# TemperatureSensorBlock.net
KiCad netlist of a schematic drawn in Altium Designer
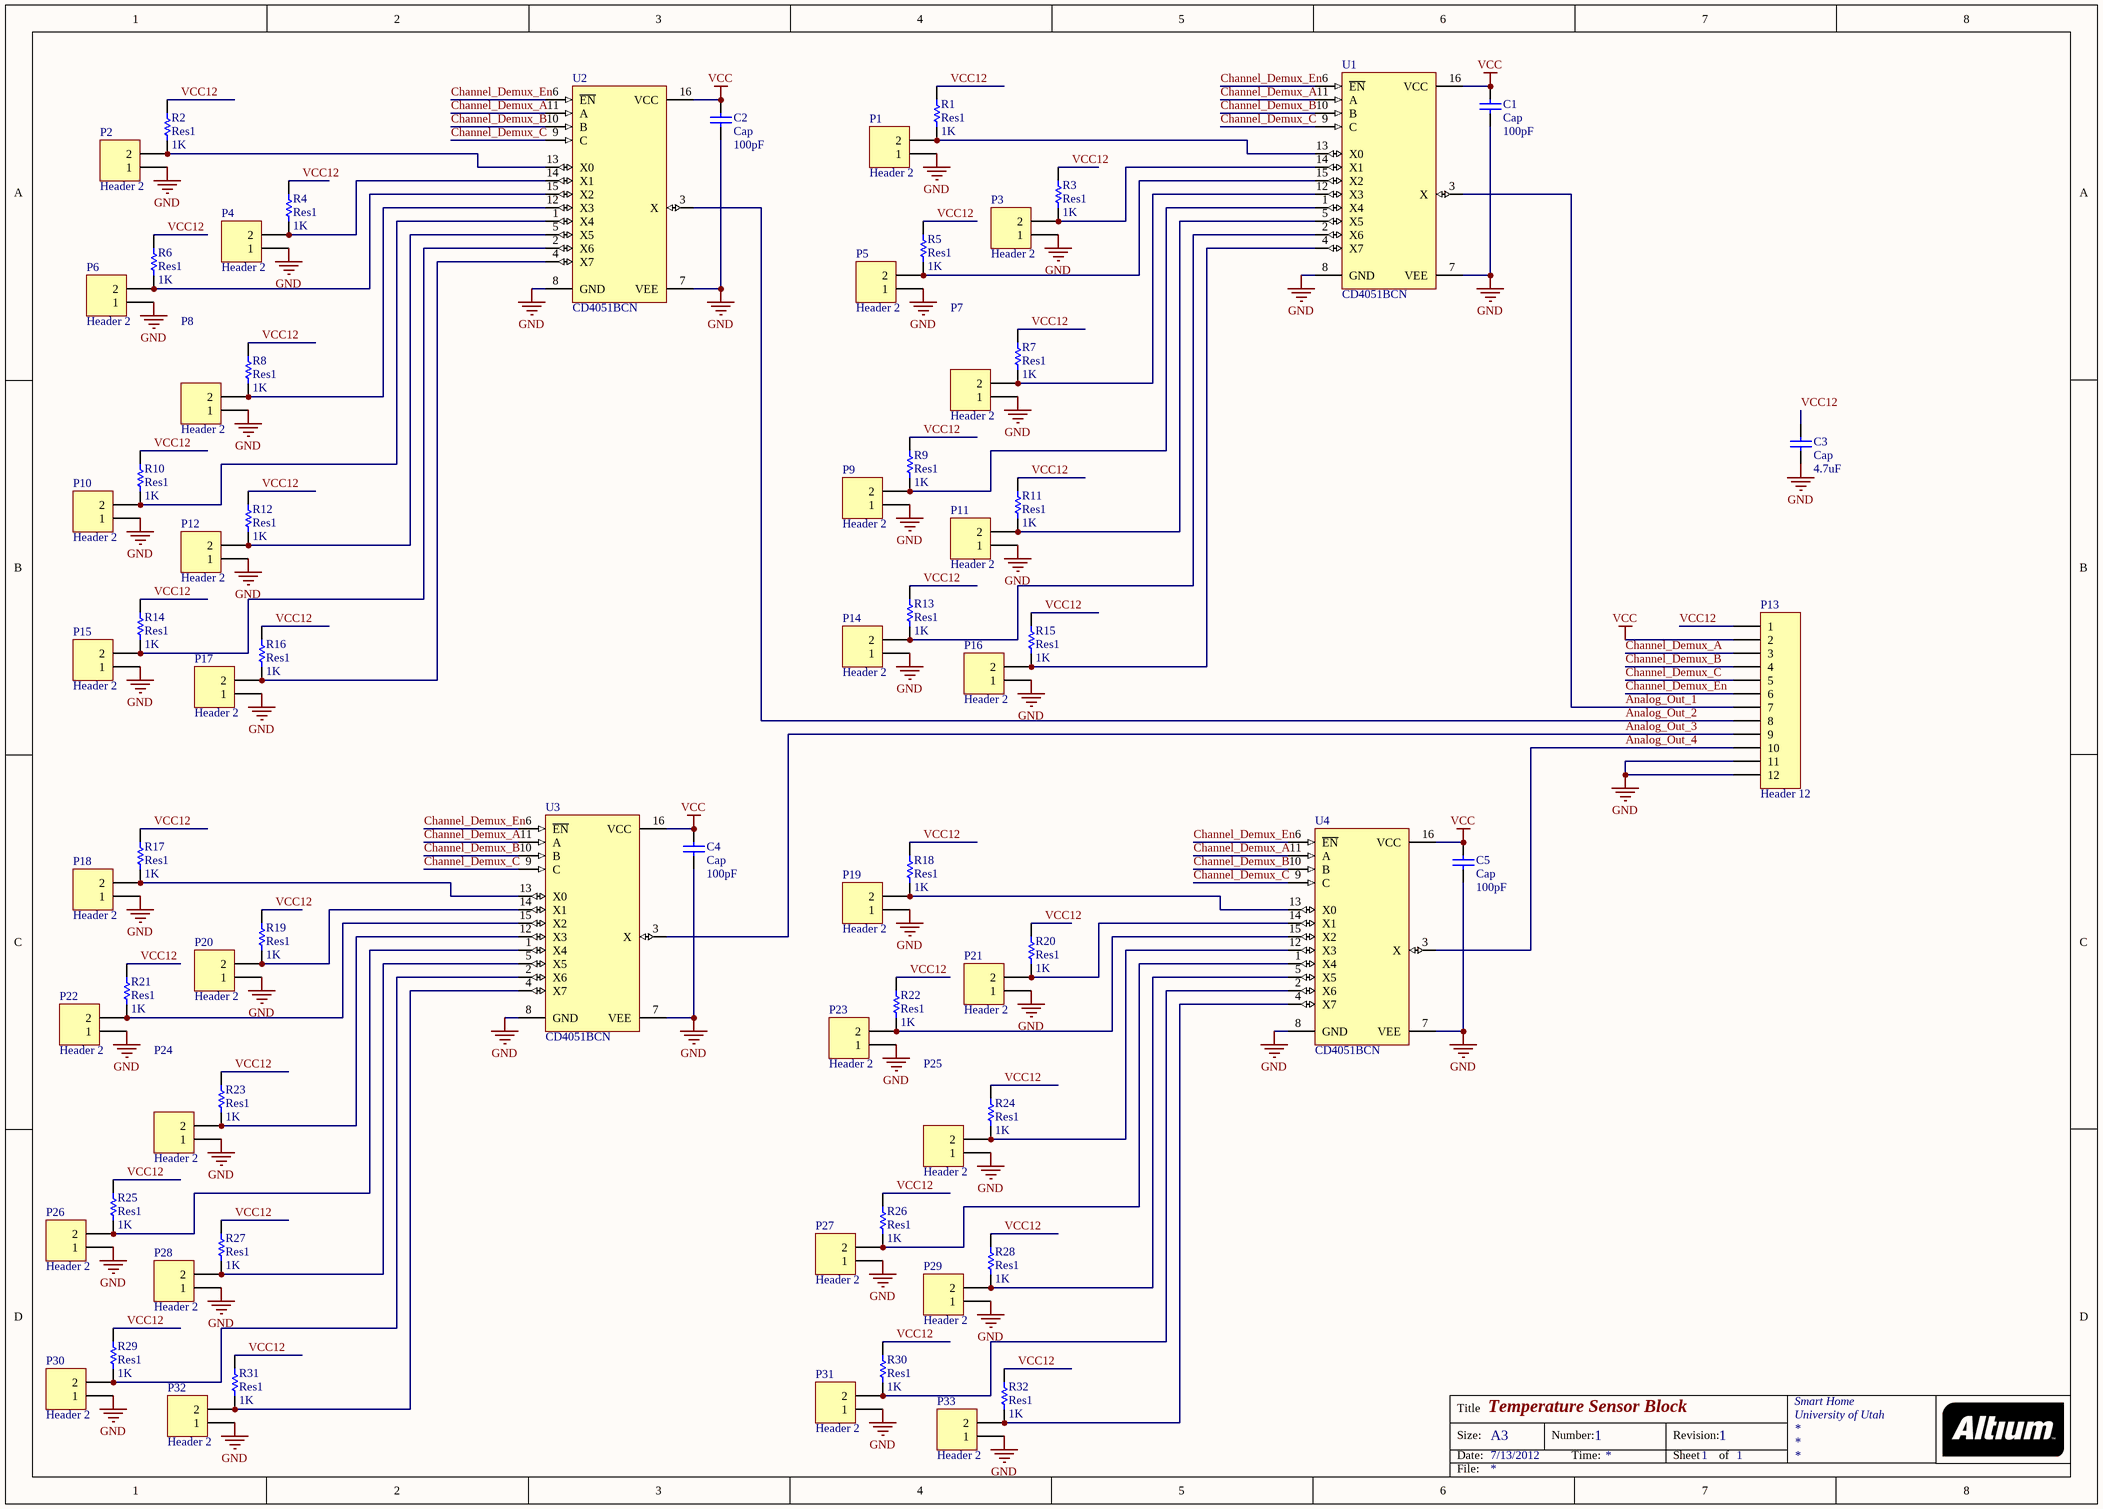
[diagram p0: TemperatureSensorBlock.SchDoc]

(export (version "E")
  (design (tool "Eeschema 10.0.6"))
  (components
    (comp (ref "C1")
      (value "Cap")
      (footprint "RAD-0.3")
      (description "Capacitor")
      (fields (field (name "ALTIUM_VALUE") "100pF") (field (name "PUBLISHER") "Altium Limited"))
      (libsource (lib "Miscellaneous Devices") (part "Cap"))
    )
    (comp (ref "C2")
      (value "Cap")
      (footprint "RAD-0.3")
      (description "Capacitor")
      (fields (field (name "ALTIUM_VALUE") "100pF") (field (name "PUBLISHER") "Altium Limited"))
      (libsource (lib "Miscellaneous Devices") (part "Cap"))
    )
    (comp (ref "C3")
      (value "Cap")
      (footprint "RAD-0.3")
      (description "Capacitor")
      (fields (field (name "ALTIUM_VALUE") "4.7uF") (field (name "PUBLISHER") "Altium Limited"))
      (libsource (lib "Miscellaneous Devices") (part "Cap"))
    )
    (comp (ref "C4")
      (value "Cap")
      (footprint "RAD-0.3")
      (description "Capacitor")
      (fields (field (name "ALTIUM_VALUE") "100pF") (field (name "PUBLISHER") "Altium Limited"))
      (libsource (lib "Miscellaneous Devices") (part "Cap"))
    )
    (comp (ref "C5")
      (value "Cap")
      (footprint "RAD-0.3")
      (description "Capacitor")
      (fields (field (name "ALTIUM_VALUE") "100pF") (field (name "PUBLISHER") "Altium Limited"))
      (libsource (lib "Miscellaneous Devices") (part "Cap"))
    )
    (comp (ref "P1")
      (value "Header 2")
      (footprint "HDR1X2")
      (description "Header, 2-Pin")
      (fields (field (name "PUBLISHER") "Altium Limited"))
      (libsource (lib "Miscellaneous Connectors") (part "Header 2"))
    )
    (comp (ref "P2")
      (value "Header 2")
      (footprint "HDR1X2")
      (description "Header, 2-Pin")
      (fields (field (name "PUBLISHER") "Altium Limited"))
      (libsource (lib "Miscellaneous Connectors") (part "Header 2"))
    )
    (comp (ref "P3")
      (value "Header 2")
      (footprint "HDR1X2")
      (description "Header, 2-Pin")
      (fields (field (name "PUBLISHER") "Altium Limited"))
      (libsource (lib "Miscellaneous Connectors") (part "Header 2"))
    )
    (comp (ref "P4")
      (value "Header 2")
      (footprint "HDR1X2")
      (description "Header, 2-Pin")
      (fields (field (name "PUBLISHER") "Altium Limited"))
      (libsource (lib "Miscellaneous Connectors") (part "Header 2"))
    )
    (comp (ref "P5")
      (value "Header 2")
      (footprint "HDR1X2")
      (description "Header, 2-Pin")
      (fields (field (name "PUBLISHER") "Altium Limited"))
      (libsource (lib "Miscellaneous Connectors") (part "Header 2"))
    )
    (comp (ref "P6")
      (value "Header 2")
      (footprint "HDR1X2")
      (description "Header, 2-Pin")
      (fields (field (name "PUBLISHER") "Altium Limited"))
      (libsource (lib "Miscellaneous Connectors") (part "Header 2"))
    )
    (comp (ref "P7")
      (value "Header 2")
      (footprint "HDR1X2")
      (description "Header, 2-Pin")
      (fields (field (name "PUBLISHER") "Altium Limited"))
      (libsource (lib "Miscellaneous Connectors") (part "Header 2"))
    )
    (comp (ref "P8")
      (value "Header 2")
      (footprint "HDR1X2")
      (description "Header, 2-Pin")
      (fields (field (name "PUBLISHER") "Altium Limited"))
      (libsource (lib "Miscellaneous Connectors") (part "Header 2"))
    )
    (comp (ref "P9")
      (value "Header 2")
      (footprint "HDR1X2")
      (description "Header, 2-Pin")
      (fields (field (name "PUBLISHER") "Altium Limited"))
      (libsource (lib "Miscellaneous Connectors") (part "Header 2"))
    )
    (comp (ref "P10")
      (value "Header 2")
      (footprint "HDR1X2")
      (description "Header, 2-Pin")
      (fields (field (name "PUBLISHER") "Altium Limited"))
      (libsource (lib "Miscellaneous Connectors") (part "Header 2"))
    )
    (comp (ref "P11")
      (value "Header 2")
      (footprint "HDR1X2")
      (description "Header, 2-Pin")
      (fields (field (name "PUBLISHER") "Altium Limited"))
      (libsource (lib "Miscellaneous Connectors") (part "Header 2"))
    )
    (comp (ref "P12")
      (value "Header 2")
      (footprint "HDR1X2")
      (description "Header, 2-Pin")
      (fields (field (name "PUBLISHER") "Altium Limited"))
      (libsource (lib "Miscellaneous Connectors") (part "Header 2"))
    )
    (comp (ref "P13")
      (value "Header 12")
      (footprint "HDR1X12")
      (description "Header, 12-Pin")
      (fields (field (name "PUBLISHER") "Altium Limited"))
      (libsource (lib "Miscellaneous Connectors") (part "Header 12"))
    )
    (comp (ref "P14")
      (value "Header 2")
      (footprint "HDR1X2")
      (description "Header, 2-Pin")
      (fields (field (name "PUBLISHER") "Altium Limited"))
      (libsource (lib "Miscellaneous Connectors") (part "Header 2"))
    )
    (comp (ref "P15")
      (value "Header 2")
      (footprint "HDR1X2")
      (description "Header, 2-Pin")
      (fields (field (name "PUBLISHER") "Altium Limited"))
      (libsource (lib "Miscellaneous Connectors") (part "Header 2"))
    )
    (comp (ref "P16")
      (value "Header 2")
      (footprint "HDR1X2")
      (description "Header, 2-Pin")
      (fields (field (name "PUBLISHER") "Altium Limited"))
      (libsource (lib "Miscellaneous Connectors") (part "Header 2"))
    )
    (comp (ref "P17")
      (value "Header 2")
      (footprint "HDR1X2")
      (description "Header, 2-Pin")
      (fields (field (name "PUBLISHER") "Altium Limited"))
      (libsource (lib "Miscellaneous Connectors") (part "Header 2"))
    )
    (comp (ref "P18")
      (value "Header 2")
      (footprint "HDR1X2")
      (description "Header, 2-Pin")
      (fields (field (name "PUBLISHER") "Altium Limited"))
      (libsource (lib "Miscellaneous Connectors") (part "Header 2"))
    )
    (comp (ref "P19")
      (value "Header 2")
      (footprint "HDR1X2")
      (description "Header, 2-Pin")
      (fields (field (name "PUBLISHER") "Altium Limited"))
      (libsource (lib "Miscellaneous Connectors") (part "Header 2"))
    )
    (comp (ref "P20")
      (value "Header 2")
      (footprint "HDR1X2")
      (description "Header, 2-Pin")
      (fields (field (name "PUBLISHER") "Altium Limited"))
      (libsource (lib "Miscellaneous Connectors") (part "Header 2"))
    )
    (comp (ref "P21")
      (value "Header 2")
      (footprint "HDR1X2")
      (description "Header, 2-Pin")
      (fields (field (name "PUBLISHER") "Altium Limited"))
      (libsource (lib "Miscellaneous Connectors") (part "Header 2"))
    )
    (comp (ref "P22")
      (value "Header 2")
      (footprint "HDR1X2")
      (description "Header, 2-Pin")
      (fields (field (name "PUBLISHER") "Altium Limited"))
      (libsource (lib "Miscellaneous Connectors") (part "Header 2"))
    )
    (comp (ref "P23")
      (value "Header 2")
      (footprint "HDR1X2")
      (description "Header, 2-Pin")
      (fields (field (name "PUBLISHER") "Altium Limited"))
      (libsource (lib "Miscellaneous Connectors") (part "Header 2"))
    )
    (comp (ref "P24")
      (value "Header 2")
      (footprint "HDR1X2")
      (description "Header, 2-Pin")
      (fields (field (name "PUBLISHER") "Altium Limited"))
      (libsource (lib "Miscellaneous Connectors") (part "Header 2"))
    )
    (comp (ref "P25")
      (value "Header 2")
      (footprint "HDR1X2")
      (description "Header, 2-Pin")
      (fields (field (name "PUBLISHER") "Altium Limited"))
      (libsource (lib "Miscellaneous Connectors") (part "Header 2"))
    )
    (comp (ref "P26")
      (value "Header 2")
      (footprint "HDR1X2")
      (description "Header, 2-Pin")
      (fields (field (name "PUBLISHER") "Altium Limited"))
      (libsource (lib "Miscellaneous Connectors") (part "Header 2"))
    )
    (comp (ref "P27")
      (value "Header 2")
      (footprint "HDR1X2")
      (description "Header, 2-Pin")
      (fields (field (name "PUBLISHER") "Altium Limited"))
      (libsource (lib "Miscellaneous Connectors") (part "Header 2"))
    )
    (comp (ref "P28")
      (value "Header 2")
      (footprint "HDR1X2")
      (description "Header, 2-Pin")
      (fields (field (name "PUBLISHER") "Altium Limited"))
      (libsource (lib "Miscellaneous Connectors") (part "Header 2"))
    )
    (comp (ref "P29")
      (value "Header 2")
      (footprint "HDR1X2")
      (description "Header, 2-Pin")
      (fields (field (name "PUBLISHER") "Altium Limited"))
      (libsource (lib "Miscellaneous Connectors") (part "Header 2"))
    )
    (comp (ref "P30")
      (value "Header 2")
      (footprint "HDR1X2")
      (description "Header, 2-Pin")
      (fields (field (name "PUBLISHER") "Altium Limited"))
      (libsource (lib "Miscellaneous Connectors") (part "Header 2"))
    )
    (comp (ref "P31")
      (value "Header 2")
      (footprint "HDR1X2")
      (description "Header, 2-Pin")
      (fields (field (name "PUBLISHER") "Altium Limited"))
      (libsource (lib "Miscellaneous Connectors") (part "Header 2"))
    )
    (comp (ref "P32")
      (value "Header 2")
      (footprint "HDR1X2")
      (description "Header, 2-Pin")
      (fields (field (name "PUBLISHER") "Altium Limited"))
      (libsource (lib "Miscellaneous Connectors") (part "Header 2"))
    )
    (comp (ref "P33")
      (value "Header 2")
      (footprint "HDR1X2")
      (description "Header, 2-Pin")
      (fields (field (name "PUBLISHER") "Altium Limited"))
      (libsource (lib "Miscellaneous Connectors") (part "Header 2"))
    )
    (comp (ref "R1")
      (value "Res1")
      (footprint "AXIAL-0.3")
      (description "Resistor")
      (fields (field (name "ALTIUM_VALUE") "1K") (field (name "PUBLISHER") "Altium Limited"))
      (libsource (lib "Miscellaneous Devices") (part "Res1"))
    )
    (comp (ref "R2")
      (value "Res1")
      (footprint "AXIAL-0.3")
      (description "Resistor")
      (fields (field (name "ALTIUM_VALUE") "1K") (field (name "PUBLISHER") "Altium Limited"))
      (libsource (lib "Miscellaneous Devices") (part "Res1"))
    )
    (comp (ref "R3")
      (value "Res1")
      (footprint "AXIAL-0.3")
      (description "Resistor")
      (fields (field (name "ALTIUM_VALUE") "1K") (field (name "PUBLISHER") "Altium Limited"))
      (libsource (lib "Miscellaneous Devices") (part "Res1"))
    )
    (comp (ref "R4")
      (value "Res1")
      (footprint "AXIAL-0.3")
      (description "Resistor")
      (fields (field (name "ALTIUM_VALUE") "1K") (field (name "PUBLISHER") "Altium Limited"))
      (libsource (lib "Miscellaneous Devices") (part "Res1"))
    )
    (comp (ref "R5")
      (value "Res1")
      (footprint "AXIAL-0.3")
      (description "Resistor")
      (fields (field (name "ALTIUM_VALUE") "1K") (field (name "PUBLISHER") "Altium Limited"))
      (libsource (lib "Miscellaneous Devices") (part "Res1"))
    )
    (comp (ref "R6")
      (value "Res1")
      (footprint "AXIAL-0.3")
      (description "Resistor")
      (fields (field (name "ALTIUM_VALUE") "1K") (field (name "PUBLISHER") "Altium Limited"))
      (libsource (lib "Miscellaneous Devices") (part "Res1"))
    )
    (comp (ref "R7")
      (value "Res1")
      (footprint "AXIAL-0.3")
      (description "Resistor")
      (fields (field (name "ALTIUM_VALUE") "1K") (field (name "PUBLISHER") "Altium Limited"))
      (libsource (lib "Miscellaneous Devices") (part "Res1"))
    )
    (comp (ref "R8")
      (value "Res1")
      (footprint "AXIAL-0.3")
      (description "Resistor")
      (fields (field (name "ALTIUM_VALUE") "1K") (field (name "PUBLISHER") "Altium Limited"))
      (libsource (lib "Miscellaneous Devices") (part "Res1"))
    )
    (comp (ref "R9")
      (value "Res1")
      (footprint "AXIAL-0.3")
      (description "Resistor")
      (fields (field (name "ALTIUM_VALUE") "1K") (field (name "PUBLISHER") "Altium Limited"))
      (libsource (lib "Miscellaneous Devices") (part "Res1"))
    )
    (comp (ref "R10")
      (value "Res1")
      (footprint "AXIAL-0.3")
      (description "Resistor")
      (fields (field (name "ALTIUM_VALUE") "1K") (field (name "PUBLISHER") "Altium Limited"))
      (libsource (lib "Miscellaneous Devices") (part "Res1"))
    )
    (comp (ref "R11")
      (value "Res1")
      (footprint "AXIAL-0.3")
      (description "Resistor")
      (fields (field (name "ALTIUM_VALUE") "1K") (field (name "PUBLISHER") "Altium Limited"))
      (libsource (lib "Miscellaneous Devices") (part "Res1"))
    )
    (comp (ref "R12")
      (value "Res1")
      (footprint "AXIAL-0.3")
      (description "Resistor")
      (fields (field (name "ALTIUM_VALUE") "1K") (field (name "PUBLISHER") "Altium Limited"))
      (libsource (lib "Miscellaneous Devices") (part "Res1"))
    )
    (comp (ref "R13")
      (value "Res1")
      (footprint "AXIAL-0.3")
      (description "Resistor")
      (fields (field (name "ALTIUM_VALUE") "1K") (field (name "PUBLISHER") "Altium Limited"))
      (libsource (lib "Miscellaneous Devices") (part "Res1"))
    )
    (comp (ref "R14")
      (value "Res1")
      (footprint "AXIAL-0.3")
      (description "Resistor")
      (fields (field (name "ALTIUM_VALUE") "1K") (field (name "PUBLISHER") "Altium Limited"))
      (libsource (lib "Miscellaneous Devices") (part "Res1"))
    )
    (comp (ref "R15")
      (value "Res1")
      (footprint "AXIAL-0.3")
      (description "Resistor")
      (fields (field (name "ALTIUM_VALUE") "1K") (field (name "PUBLISHER") "Altium Limited"))
      (libsource (lib "Miscellaneous Devices") (part "Res1"))
    )
    (comp (ref "R16")
      (value "Res1")
      (footprint "AXIAL-0.3")
      (description "Resistor")
      (fields (field (name "ALTIUM_VALUE") "1K") (field (name "PUBLISHER") "Altium Limited"))
      (libsource (lib "Miscellaneous Devices") (part "Res1"))
    )
    (comp (ref "R17")
      (value "Res1")
      (footprint "AXIAL-0.3")
      (description "Resistor")
      (fields (field (name "ALTIUM_VALUE") "1K") (field (name "PUBLISHER") "Altium Limited"))
      (libsource (lib "Miscellaneous Devices") (part "Res1"))
    )
    (comp (ref "R18")
      (value "Res1")
      (footprint "AXIAL-0.3")
      (description "Resistor")
      (fields (field (name "ALTIUM_VALUE") "1K") (field (name "PUBLISHER") "Altium Limited"))
      (libsource (lib "Miscellaneous Devices") (part "Res1"))
    )
    (comp (ref "R19")
      (value "Res1")
      (footprint "AXIAL-0.3")
      (description "Resistor")
      (fields (field (name "ALTIUM_VALUE") "1K") (field (name "PUBLISHER") "Altium Limited"))
      (libsource (lib "Miscellaneous Devices") (part "Res1"))
    )
    (comp (ref "R20")
      (value "Res1")
      (footprint "AXIAL-0.3")
      (description "Resistor")
      (fields (field (name "ALTIUM_VALUE") "1K") (field (name "PUBLISHER") "Altium Limited"))
      (libsource (lib "Miscellaneous Devices") (part "Res1"))
    )
    (comp (ref "R21")
      (value "Res1")
      (footprint "AXIAL-0.3")
      (description "Resistor")
      (fields (field (name "ALTIUM_VALUE") "1K") (field (name "PUBLISHER") "Altium Limited"))
      (libsource (lib "Miscellaneous Devices") (part "Res1"))
    )
    (comp (ref "R22")
      (value "Res1")
      (footprint "AXIAL-0.3")
      (description "Resistor")
      (fields (field (name "ALTIUM_VALUE") "1K") (field (name "PUBLISHER") "Altium Limited"))
      (libsource (lib "Miscellaneous Devices") (part "Res1"))
    )
    (comp (ref "R23")
      (value "Res1")
      (footprint "AXIAL-0.3")
      (description "Resistor")
      (fields (field (name "ALTIUM_VALUE") "1K") (field (name "PUBLISHER") "Altium Limited"))
      (libsource (lib "Miscellaneous Devices") (part "Res1"))
    )
    (comp (ref "R24")
      (value "Res1")
      (footprint "AXIAL-0.3")
      (description "Resistor")
      (fields (field (name "ALTIUM_VALUE") "1K") (field (name "PUBLISHER") "Altium Limited"))
      (libsource (lib "Miscellaneous Devices") (part "Res1"))
    )
    (comp (ref "R25")
      (value "Res1")
      (footprint "AXIAL-0.3")
      (description "Resistor")
      (fields (field (name "ALTIUM_VALUE") "1K") (field (name "PUBLISHER") "Altium Limited"))
      (libsource (lib "Miscellaneous Devices") (part "Res1"))
    )
    (comp (ref "R26")
      (value "Res1")
      (footprint "AXIAL-0.3")
      (description "Resistor")
      (fields (field (name "ALTIUM_VALUE") "1K") (field (name "PUBLISHER") "Altium Limited"))
      (libsource (lib "Miscellaneous Devices") (part "Res1"))
    )
    (comp (ref "R27")
      (value "Res1")
      (footprint "AXIAL-0.3")
      (description "Resistor")
      (fields (field (name "ALTIUM_VALUE") "1K") (field (name "PUBLISHER") "Altium Limited"))
      (libsource (lib "Miscellaneous Devices") (part "Res1"))
    )
    (comp (ref "R28")
      (value "Res1")
      (footprint "AXIAL-0.3")
      (description "Resistor")
      (fields (field (name "ALTIUM_VALUE") "1K") (field (name "PUBLISHER") "Altium Limited"))
      (libsource (lib "Miscellaneous Devices") (part "Res1"))
    )
    (comp (ref "R29")
      (value "Res1")
      (footprint "AXIAL-0.3")
      (description "Resistor")
      (fields (field (name "ALTIUM_VALUE") "1K") (field (name "PUBLISHER") "Altium Limited"))
      (libsource (lib "Miscellaneous Devices") (part "Res1"))
    )
    (comp (ref "R30")
      (value "Res1")
      (footprint "AXIAL-0.3")
      (description "Resistor")
      (fields (field (name "ALTIUM_VALUE") "1K") (field (name "PUBLISHER") "Altium Limited"))
      (libsource (lib "Miscellaneous Devices") (part "Res1"))
    )
    (comp (ref "R31")
      (value "Res1")
      (footprint "AXIAL-0.3")
      (description "Resistor")
      (fields (field (name "ALTIUM_VALUE") "1K") (field (name "PUBLISHER") "Altium Limited"))
      (libsource (lib "Miscellaneous Devices") (part "Res1"))
    )
    (comp (ref "R32")
      (value "Res1")
      (footprint "AXIAL-0.3")
      (description "Resistor")
      (fields (field (name "ALTIUM_VALUE") "1K") (field (name "PUBLISHER") "Altium Limited"))
      (libsource (lib "Miscellaneous Devices") (part "Res1"))
    )
    (comp (ref "U1")
      (value "CD4051BCN")
      (footprint "N16E")
      (description "8-Channel Analog Multiplexer/Demultiplexer")
      (fields (field (name "PUBLISHER") "Altium Limited"))
      (libsource (lib "FSC Logic Multiplexer") (part "CD4051BCN"))
    )
    (comp (ref "U2")
      (value "CD4051BCN")
      (footprint "N16E")
      (description "8-Channel Analog Multiplexer/Demultiplexer")
      (fields (field (name "PUBLISHER") "Altium Limited"))
      (libsource (lib "FSC Logic Multiplexer") (part "CD4051BCN"))
    )
    (comp (ref "U3")
      (value "CD4051BCN")
      (footprint "N16E")
      (description "8-Channel Analog Multiplexer/Demultiplexer")
      (fields (field (name "PUBLISHER") "Altium Limited"))
      (libsource (lib "FSC Logic Multiplexer") (part "CD4051BCN"))
    )
    (comp (ref "U4")
      (value "CD4051BCN")
      (footprint "N16E")
      (description "8-Channel Analog Multiplexer/Demultiplexer")
      (fields (field (name "PUBLISHER") "Altium Limited"))
      (libsource (lib "FSC Logic Multiplexer") (part "CD4051BCN"))
    )
  )
  (nets
    (net (code "1") (name "/Analog_Out_1") (class "Default")
      (node (ref "P13") (pin "7") (pinfunction "7_7") (pintype "passive"))
      (node (ref "U1") (pin "3") (pinfunction "X_3") (pintype "bidirectional"))
    )
    (net (code "2") (name "/Analog_Out_2") (class "Default")
      (node (ref "P13") (pin "8") (pinfunction "8_8") (pintype "passive"))
      (node (ref "U2") (pin "3") (pinfunction "X_3") (pintype "bidirectional"))
    )
    (net (code "3") (name "/Analog_Out_3") (class "Default")
      (node (ref "P13") (pin "9") (pinfunction "9_9") (pintype "passive"))
      (node (ref "U3") (pin "3") (pinfunction "X_3") (pintype "bidirectional"))
    )
    (net (code "4") (name "/Analog_Out_4") (class "Default")
      (node (ref "P13") (pin "10") (pinfunction "10_10") (pintype "passive"))
      (node (ref "U4") (pin "3") (pinfunction "X_3") (pintype "bidirectional"))
    )
    (net (code "5") (name "/Channel_Demux_A") (class "Default")
      (node (ref "P13") (pin "3") (pinfunction "3_3") (pintype "passive"))
      (node (ref "U1") (pin "11") (pinfunction "A_11") (pintype "input"))
      (node (ref "U2") (pin "11") (pinfunction "A_11") (pintype "input"))
      (node (ref "U3") (pin "11") (pinfunction "A_11") (pintype "input"))
      (node (ref "U4") (pin "11") (pinfunction "A_11") (pintype "input"))
    )
    (net (code "6") (name "/Channel_Demux_B") (class "Default")
      (node (ref "P13") (pin "4") (pinfunction "4_4") (pintype "passive"))
      (node (ref "U1") (pin "10") (pinfunction "B_10") (pintype "input"))
      (node (ref "U2") (pin "10") (pinfunction "B_10") (pintype "input"))
      (node (ref "U3") (pin "10") (pinfunction "B_10") (pintype "input"))
      (node (ref "U4") (pin "10") (pinfunction "B_10") (pintype "input"))
    )
    (net (code "7") (name "/Channel_Demux_C") (class "Default")
      (node (ref "P13") (pin "5") (pinfunction "5_5") (pintype "passive"))
      (node (ref "U1") (pin "9") (pinfunction "C_9") (pintype "input"))
      (node (ref "U2") (pin "9") (pinfunction "C_9") (pintype "input"))
      (node (ref "U3") (pin "9") (pinfunction "C_9") (pintype "input"))
      (node (ref "U4") (pin "9") (pinfunction "C_9") (pintype "input"))
    )
    (net (code "8") (name "/Channel_Demux_En") (class "Default")
      (node (ref "P13") (pin "6") (pinfunction "6_6") (pintype "passive"))
      (node (ref "U1") (pin "6") (pinfunction "~{EN}_6") (pintype "input"))
      (node (ref "U2") (pin "6") (pinfunction "~{EN}_6") (pintype "input"))
      (node (ref "U3") (pin "6") (pinfunction "~{EN}_6") (pintype "input"))
      (node (ref "U4") (pin "6") (pinfunction "~{EN}_6") (pintype "input"))
    )
    (net (code "9") (name "/VCC12") (class "Default")
      (node (ref "C3") (pin "2") (pinfunction "2_2") (pintype "passive"))
      (node (ref "P13") (pin "1") (pinfunction "1_1") (pintype "passive"))
      (node (ref "R1") (pin "2") (pinfunction "2_2") (pintype "passive"))
      (node (ref "R10") (pin "2") (pinfunction "2_2") (pintype "passive"))
      (node (ref "R11") (pin "2") (pinfunction "2_2") (pintype "passive"))
      (node (ref "R12") (pin "2") (pinfunction "2_2") (pintype "passive"))
      (node (ref "R13") (pin "2") (pinfunction "2_2") (pintype "passive"))
      (node (ref "R14") (pin "2") (pinfunction "2_2") (pintype "passive"))
      (node (ref "R15") (pin "2") (pinfunction "2_2") (pintype "passive"))
      (node (ref "R16") (pin "2") (pinfunction "2_2") (pintype "passive"))
      (node (ref "R17") (pin "2") (pinfunction "2_2") (pintype "passive"))
      (node (ref "R18") (pin "2") (pinfunction "2_2") (pintype "passive"))
      (node (ref "R19") (pin "2") (pinfunction "2_2") (pintype "passive"))
      (node (ref "R2") (pin "2") (pinfunction "2_2") (pintype "passive"))
      (node (ref "R20") (pin "2") (pinfunction "2_2") (pintype "passive"))
      (node (ref "R21") (pin "2") (pinfunction "2_2") (pintype "passive"))
      (node (ref "R22") (pin "2") (pinfunction "2_2") (pintype "passive"))
      (node (ref "R23") (pin "2") (pinfunction "2_2") (pintype "passive"))
      (node (ref "R24") (pin "2") (pinfunction "2_2") (pintype "passive"))
      (node (ref "R25") (pin "2") (pinfunction "2_2") (pintype "passive"))
      (node (ref "R26") (pin "2") (pinfunction "2_2") (pintype "passive"))
      (node (ref "R27") (pin "2") (pinfunction "2_2") (pintype "passive"))
      (node (ref "R28") (pin "2") (pinfunction "2_2") (pintype "passive"))
      (node (ref "R29") (pin "2") (pinfunction "2_2") (pintype "passive"))
      (node (ref "R3") (pin "2") (pinfunction "2_2") (pintype "passive"))
      (node (ref "R30") (pin "2") (pinfunction "2_2") (pintype "passive"))
      (node (ref "R31") (pin "2") (pinfunction "2_2") (pintype "passive"))
      (node (ref "R32") (pin "2") (pinfunction "2_2") (pintype "passive"))
      (node (ref "R4") (pin "2") (pinfunction "2_2") (pintype "passive"))
      (node (ref "R5") (pin "2") (pinfunction "2_2") (pintype "passive"))
      (node (ref "R6") (pin "2") (pinfunction "2_2") (pintype "passive"))
      (node (ref "R7") (pin "2") (pinfunction "2_2") (pintype "passive"))
      (node (ref "R8") (pin "2") (pinfunction "2_2") (pintype "passive"))
      (node (ref "R9") (pin "2") (pinfunction "2_2") (pintype "passive"))
    )
    (net (code "10") (name "GND") (class "Default")
      (node (ref "C1") (pin "1") (pinfunction "1_1") (pintype "passive"))
      (node (ref "C2") (pin "1") (pinfunction "1_1") (pintype "passive"))
      (node (ref "C3") (pin "1") (pinfunction "1_1") (pintype "passive"))
      (node (ref "C4") (pin "1") (pinfunction "1_1") (pintype "passive"))
      (node (ref "C5") (pin "1") (pinfunction "1_1") (pintype "passive"))
      (node (ref "P1") (pin "1") (pinfunction "1_1") (pintype "passive"))
      (node (ref "P10") (pin "1") (pinfunction "1_1") (pintype "passive"))
      (node (ref "P11") (pin "1") (pinfunction "1_1") (pintype "passive"))
      (node (ref "P12") (pin "1") (pinfunction "1_1") (pintype "passive"))
      (node (ref "P13") (pin "11") (pinfunction "11_11") (pintype "passive"))
      (node (ref "P13") (pin "12") (pinfunction "12_12") (pintype "passive"))
      (node (ref "P14") (pin "1") (pinfunction "1_1") (pintype "passive"))
      (node (ref "P15") (pin "1") (pinfunction "1_1") (pintype "passive"))
      (node (ref "P16") (pin "1") (pinfunction "1_1") (pintype "passive"))
      (node (ref "P17") (pin "1") (pinfunction "1_1") (pintype "passive"))
      (node (ref "P18") (pin "1") (pinfunction "1_1") (pintype "passive"))
      (node (ref "P19") (pin "1") (pinfunction "1_1") (pintype "passive"))
      (node (ref "P2") (pin "1") (pinfunction "1_1") (pintype "passive"))
      (node (ref "P20") (pin "1") (pinfunction "1_1") (pintype "passive"))
      (node (ref "P21") (pin "1") (pinfunction "1_1") (pintype "passive"))
      (node (ref "P22") (pin "1") (pinfunction "1_1") (pintype "passive"))
      (node (ref "P23") (pin "1") (pinfunction "1_1") (pintype "passive"))
      (node (ref "P24") (pin "1") (pinfunction "1_1") (pintype "passive"))
      (node (ref "P25") (pin "1") (pinfunction "1_1") (pintype "passive"))
      (node (ref "P26") (pin "1") (pinfunction "1_1") (pintype "passive"))
      (node (ref "P27") (pin "1") (pinfunction "1_1") (pintype "passive"))
      (node (ref "P28") (pin "1") (pinfunction "1_1") (pintype "passive"))
      (node (ref "P29") (pin "1") (pinfunction "1_1") (pintype "passive"))
      (node (ref "P3") (pin "1") (pinfunction "1_1") (pintype "passive"))
      (node (ref "P30") (pin "1") (pinfunction "1_1") (pintype "passive"))
      (node (ref "P31") (pin "1") (pinfunction "1_1") (pintype "passive"))
      (node (ref "P32") (pin "1") (pinfunction "1_1") (pintype "passive"))
      (node (ref "P33") (pin "1") (pinfunction "1_1") (pintype "passive"))
      (node (ref "P4") (pin "1") (pinfunction "1_1") (pintype "passive"))
      (node (ref "P5") (pin "1") (pinfunction "1_1") (pintype "passive"))
      (node (ref "P6") (pin "1") (pinfunction "1_1") (pintype "passive"))
      (node (ref "P7") (pin "1") (pinfunction "1_1") (pintype "passive"))
      (node (ref "P8") (pin "1") (pinfunction "1_1") (pintype "passive"))
      (node (ref "P9") (pin "1") (pinfunction "1_1") (pintype "passive"))
      (node (ref "U1") (pin "7") (pinfunction "VEE_7") (pintype "power_in"))
      (node (ref "U1") (pin "8") (pinfunction "GND_8") (pintype "power_in"))
      (node (ref "U2") (pin "7") (pinfunction "VEE_7") (pintype "power_in"))
      (node (ref "U2") (pin "8") (pinfunction "GND_8") (pintype "power_in"))
      (node (ref "U3") (pin "7") (pinfunction "VEE_7") (pintype "power_in"))
      (node (ref "U3") (pin "8") (pinfunction "GND_8") (pintype "power_in"))
      (node (ref "U4") (pin "7") (pinfunction "VEE_7") (pintype "power_in"))
      (node (ref "U4") (pin "8") (pinfunction "GND_8") (pintype "power_in"))
    )
    (net (code "11") (name "Net-(U1-X0)") (class "Default")
      (node (ref "P1") (pin "2") (pinfunction "2_2") (pintype "passive"))
      (node (ref "R1") (pin "1") (pinfunction "1_1") (pintype "passive"))
      (node (ref "U1") (pin "13") (pinfunction "X0_13") (pintype "bidirectional"))
    )
    (net (code "12") (name "Net-(U1-X1)") (class "Default")
      (node (ref "P3") (pin "2") (pinfunction "2_2") (pintype "passive"))
      (node (ref "R3") (pin "1") (pinfunction "1_1") (pintype "passive"))
      (node (ref "U1") (pin "14") (pinfunction "X1_14") (pintype "bidirectional"))
    )
    (net (code "13") (name "Net-(U1-X2)") (class "Default")
      (node (ref "P5") (pin "2") (pinfunction "2_2") (pintype "passive"))
      (node (ref "R5") (pin "1") (pinfunction "1_1") (pintype "passive"))
      (node (ref "U1") (pin "15") (pinfunction "X2_15") (pintype "bidirectional"))
    )
    (net (code "14") (name "Net-(U1-X3)") (class "Default")
      (node (ref "P7") (pin "2") (pinfunction "2_2") (pintype "passive"))
      (node (ref "R7") (pin "1") (pinfunction "1_1") (pintype "passive"))
      (node (ref "U1") (pin "12") (pinfunction "X3_12") (pintype "bidirectional"))
    )
    (net (code "15") (name "Net-(U1-X4)") (class "Default")
      (node (ref "P9") (pin "2") (pinfunction "2_2") (pintype "passive"))
      (node (ref "R9") (pin "1") (pinfunction "1_1") (pintype "passive"))
      (node (ref "U1") (pin "1") (pinfunction "X4_1") (pintype "bidirectional"))
    )
    (net (code "16") (name "Net-(U1-X5)") (class "Default")
      (node (ref "P11") (pin "2") (pinfunction "2_2") (pintype "passive"))
      (node (ref "R11") (pin "1") (pinfunction "1_1") (pintype "passive"))
      (node (ref "U1") (pin "5") (pinfunction "X5_5") (pintype "bidirectional"))
    )
    (net (code "17") (name "Net-(U1-X6)") (class "Default")
      (node (ref "P14") (pin "2") (pinfunction "2_2") (pintype "passive"))
      (node (ref "R13") (pin "1") (pinfunction "1_1") (pintype "passive"))
      (node (ref "U1") (pin "2") (pinfunction "X6_2") (pintype "bidirectional"))
    )
    (net (code "18") (name "Net-(U1-X7)") (class "Default")
      (node (ref "P16") (pin "2") (pinfunction "2_2") (pintype "passive"))
      (node (ref "R15") (pin "1") (pinfunction "1_1") (pintype "passive"))
      (node (ref "U1") (pin "4") (pinfunction "X7_4") (pintype "bidirectional"))
    )
    (net (code "19") (name "Net-(U2-X0)") (class "Default")
      (node (ref "P2") (pin "2") (pinfunction "2_2") (pintype "passive"))
      (node (ref "R2") (pin "1") (pinfunction "1_1") (pintype "passive"))
      (node (ref "U2") (pin "13") (pinfunction "X0_13") (pintype "bidirectional"))
    )
    (net (code "20") (name "Net-(U2-X1)") (class "Default")
      (node (ref "P4") (pin "2") (pinfunction "2_2") (pintype "passive"))
      (node (ref "R4") (pin "1") (pinfunction "1_1") (pintype "passive"))
      (node (ref "U2") (pin "14") (pinfunction "X1_14") (pintype "bidirectional"))
    )
    (net (code "21") (name "Net-(U2-X2)") (class "Default")
      (node (ref "P6") (pin "2") (pinfunction "2_2") (pintype "passive"))
      (node (ref "R6") (pin "1") (pinfunction "1_1") (pintype "passive"))
      (node (ref "U2") (pin "15") (pinfunction "X2_15") (pintype "bidirectional"))
    )
    (net (code "22") (name "Net-(U2-X3)") (class "Default")
      (node (ref "P8") (pin "2") (pinfunction "2_2") (pintype "passive"))
      (node (ref "R8") (pin "1") (pinfunction "1_1") (pintype "passive"))
      (node (ref "U2") (pin "12") (pinfunction "X3_12") (pintype "bidirectional"))
    )
    (net (code "23") (name "Net-(U2-X4)") (class "Default")
      (node (ref "P10") (pin "2") (pinfunction "2_2") (pintype "passive"))
      (node (ref "R10") (pin "1") (pinfunction "1_1") (pintype "passive"))
      (node (ref "U2") (pin "1") (pinfunction "X4_1") (pintype "bidirectional"))
    )
    (net (code "24") (name "Net-(U2-X5)") (class "Default")
      (node (ref "P12") (pin "2") (pinfunction "2_2") (pintype "passive"))
      (node (ref "R12") (pin "1") (pinfunction "1_1") (pintype "passive"))
      (node (ref "U2") (pin "5") (pinfunction "X5_5") (pintype "bidirectional"))
    )
    (net (code "25") (name "Net-(U2-X6)") (class "Default")
      (node (ref "P15") (pin "2") (pinfunction "2_2") (pintype "passive"))
      (node (ref "R14") (pin "1") (pinfunction "1_1") (pintype "passive"))
      (node (ref "U2") (pin "2") (pinfunction "X6_2") (pintype "bidirectional"))
    )
    (net (code "26") (name "Net-(U2-X7)") (class "Default")
      (node (ref "P17") (pin "2") (pinfunction "2_2") (pintype "passive"))
      (node (ref "R16") (pin "1") (pinfunction "1_1") (pintype "passive"))
      (node (ref "U2") (pin "4") (pinfunction "X7_4") (pintype "bidirectional"))
    )
    (net (code "27") (name "Net-(U3-X0)") (class "Default")
      (node (ref "P18") (pin "2") (pinfunction "2_2") (pintype "passive"))
      (node (ref "R17") (pin "1") (pinfunction "1_1") (pintype "passive"))
      (node (ref "U3") (pin "13") (pinfunction "X0_13") (pintype "bidirectional"))
    )
    (net (code "28") (name "Net-(U3-X1)") (class "Default")
      (node (ref "P20") (pin "2") (pinfunction "2_2") (pintype "passive"))
      (node (ref "R19") (pin "1") (pinfunction "1_1") (pintype "passive"))
      (node (ref "U3") (pin "14") (pinfunction "X1_14") (pintype "bidirectional"))
    )
    (net (code "29") (name "Net-(U3-X2)") (class "Default")
      (node (ref "P22") (pin "2") (pinfunction "2_2") (pintype "passive"))
      (node (ref "R21") (pin "1") (pinfunction "1_1") (pintype "passive"))
      (node (ref "U3") (pin "15") (pinfunction "X2_15") (pintype "bidirectional"))
    )
    (net (code "30") (name "Net-(U3-X3)") (class "Default")
      (node (ref "P24") (pin "2") (pinfunction "2_2") (pintype "passive"))
      (node (ref "R23") (pin "1") (pinfunction "1_1") (pintype "passive"))
      (node (ref "U3") (pin "12") (pinfunction "X3_12") (pintype "bidirectional"))
    )
    (net (code "31") (name "Net-(U3-X4)") (class "Default")
      (node (ref "P26") (pin "2") (pinfunction "2_2") (pintype "passive"))
      (node (ref "R25") (pin "1") (pinfunction "1_1") (pintype "passive"))
      (node (ref "U3") (pin "1") (pinfunction "X4_1") (pintype "bidirectional"))
    )
    (net (code "32") (name "Net-(U3-X5)") (class "Default")
      (node (ref "P28") (pin "2") (pinfunction "2_2") (pintype "passive"))
      (node (ref "R27") (pin "1") (pinfunction "1_1") (pintype "passive"))
      (node (ref "U3") (pin "5") (pinfunction "X5_5") (pintype "bidirectional"))
    )
    (net (code "33") (name "Net-(U3-X6)") (class "Default")
      (node (ref "P30") (pin "2") (pinfunction "2_2") (pintype "passive"))
      (node (ref "R29") (pin "1") (pinfunction "1_1") (pintype "passive"))
      (node (ref "U3") (pin "2") (pinfunction "X6_2") (pintype "bidirectional"))
    )
    (net (code "34") (name "Net-(U3-X7)") (class "Default")
      (node (ref "P32") (pin "2") (pinfunction "2_2") (pintype "passive"))
      (node (ref "R31") (pin "1") (pinfunction "1_1") (pintype "passive"))
      (node (ref "U3") (pin "4") (pinfunction "X7_4") (pintype "bidirectional"))
    )
    (net (code "35") (name "Net-(U4-X0)") (class "Default")
      (node (ref "P19") (pin "2") (pinfunction "2_2") (pintype "passive"))
      (node (ref "R18") (pin "1") (pinfunction "1_1") (pintype "passive"))
      (node (ref "U4") (pin "13") (pinfunction "X0_13") (pintype "bidirectional"))
    )
    (net (code "36") (name "Net-(U4-X1)") (class "Default")
      (node (ref "P21") (pin "2") (pinfunction "2_2") (pintype "passive"))
      (node (ref "R20") (pin "1") (pinfunction "1_1") (pintype "passive"))
      (node (ref "U4") (pin "14") (pinfunction "X1_14") (pintype "bidirectional"))
    )
    (net (code "37") (name "Net-(U4-X2)") (class "Default")
      (node (ref "P23") (pin "2") (pinfunction "2_2") (pintype "passive"))
      (node (ref "R22") (pin "1") (pinfunction "1_1") (pintype "passive"))
      (node (ref "U4") (pin "15") (pinfunction "X2_15") (pintype "bidirectional"))
    )
    (net (code "38") (name "Net-(U4-X3)") (class "Default")
      (node (ref "P25") (pin "2") (pinfunction "2_2") (pintype "passive"))
      (node (ref "R24") (pin "1") (pinfunction "1_1") (pintype "passive"))
      (node (ref "U4") (pin "12") (pinfunction "X3_12") (pintype "bidirectional"))
    )
    (net (code "39") (name "Net-(U4-X4)") (class "Default")
      (node (ref "P27") (pin "2") (pinfunction "2_2") (pintype "passive"))
      (node (ref "R26") (pin "1") (pinfunction "1_1") (pintype "passive"))
      (node (ref "U4") (pin "1") (pinfunction "X4_1") (pintype "bidirectional"))
    )
    (net (code "40") (name "Net-(U4-X5)") (class "Default")
      (node (ref "P29") (pin "2") (pinfunction "2_2") (pintype "passive"))
      (node (ref "R28") (pin "1") (pinfunction "1_1") (pintype "passive"))
      (node (ref "U4") (pin "5") (pinfunction "X5_5") (pintype "bidirectional"))
    )
    (net (code "41") (name "Net-(U4-X6)") (class "Default")
      (node (ref "P31") (pin "2") (pinfunction "2_2") (pintype "passive"))
      (node (ref "R30") (pin "1") (pinfunction "1_1") (pintype "passive"))
      (node (ref "U4") (pin "2") (pinfunction "X6_2") (pintype "bidirectional"))
    )
    (net (code "42") (name "Net-(U4-X7)") (class "Default")
      (node (ref "P33") (pin "2") (pinfunction "2_2") (pintype "passive"))
      (node (ref "R32") (pin "1") (pinfunction "1_1") (pintype "passive"))
      (node (ref "U4") (pin "4") (pinfunction "X7_4") (pintype "bidirectional"))
    )
    (net (code "43") (name "VCC") (class "Default")
      (node (ref "C1") (pin "2") (pinfunction "2_2") (pintype "passive"))
      (node (ref "C2") (pin "2") (pinfunction "2_2") (pintype "passive"))
      (node (ref "C4") (pin "2") (pinfunction "2_2") (pintype "passive"))
      (node (ref "C5") (pin "2") (pinfunction "2_2") (pintype "passive"))
      (node (ref "P13") (pin "2") (pinfunction "2_2") (pintype "passive"))
      (node (ref "U1") (pin "16") (pinfunction "VCC_16") (pintype "power_in"))
      (node (ref "U2") (pin "16") (pinfunction "VCC_16") (pintype "power_in"))
      (node (ref "U3") (pin "16") (pinfunction "VCC_16") (pintype "power_in"))
      (node (ref "U4") (pin "16") (pinfunction "VCC_16") (pintype "power_in"))
    )
  )
)
